# PIPduino.net
KiCad netlist of a schematic drawn in EAGLE
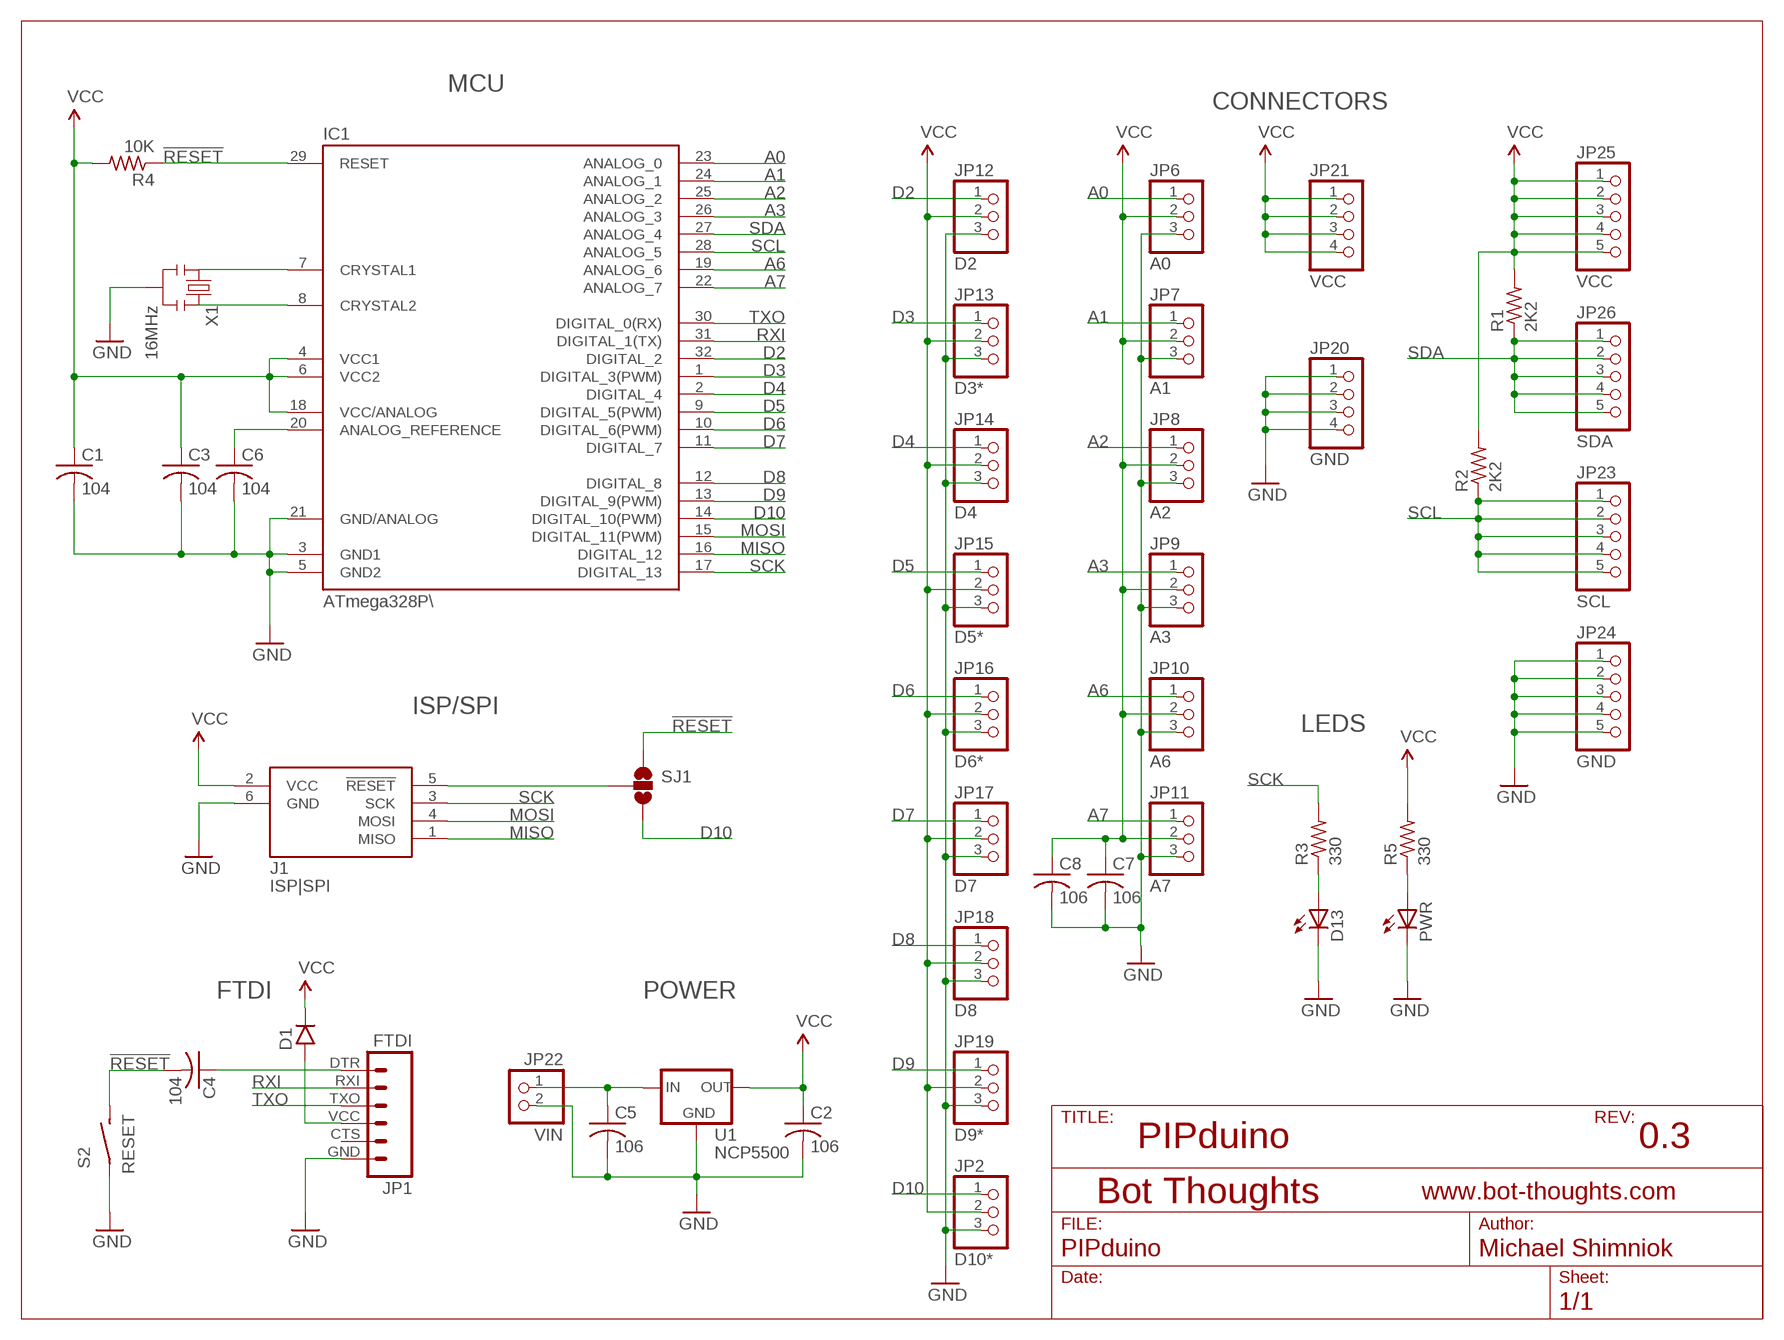
[diagram p0: schematic, sheet 1]

(export (version "E")
  (design (tool "Eeschema 10.0.6"))
  (components
    (comp (ref "C1")
      (value "104")
      (footprint "eagle-import:C0603")
      (libsource (lib "eagle-import") (part "C-USC0603"))
    )
    (comp (ref "C2")
      (value "106")
      (footprint "eagle-import:C1206")
      (libsource (lib "eagle-import") (part "C-USC1206"))
    )
    (comp (ref "C3")
      (value "104")
      (footprint "eagle-import:C0603")
      (libsource (lib "eagle-import") (part "C-USC0603"))
    )
    (comp (ref "C4")
      (value "104")
      (footprint "eagle-import:C0603")
      (libsource (lib "eagle-import") (part "C-USC0603"))
    )
    (comp (ref "C5")
      (value "106")
      (footprint "eagle-import:C1206")
      (libsource (lib "eagle-import") (part "C-USC1206"))
    )
    (comp (ref "C6")
      (value "104")
      (footprint "eagle-import:C0603")
      (libsource (lib "eagle-import") (part "C-USC0603"))
    )
    (comp (ref "C7")
      (value "106")
      (footprint "eagle-import:C1206")
      (libsource (lib "eagle-import") (part "C-USC1206"))
    )
    (comp (ref "C8")
      (value "106")
      (footprint "eagle-import:C1206")
      (libsource (lib "eagle-import") (part "C-USC1206"))
    )
    (comp (ref "D1")
      (value "DIODE_SOD123FL")
      (footprint "eagle-import:SOD123FL")
      (libsource (lib "eagle-import") (part "DIODE_SOD123FL"))
    )
    (comp (ref "D13")
      (value "LED3MM")
      (footprint "eagle-import:LED3MM")
      (libsource (lib "eagle-import") (part "LED3MM"))
    )
    (comp (ref "IC1")
      (value "ATmega328P\\")
      (footprint "eagle-import:TQFP32-08")
      (libsource (lib "eagle-import") (part "ATMEGA168-AU"))
    )
    (comp (ref "J1")
      (value "ISP|SPI")
      (footprint "eagle-import:CON6P2R")
      (libsource (lib "eagle-import") (part "AVRISP6_COMPACT"))
    )
    (comp (ref "JP1")
      (value "FTDI")
      (footprint "eagle-import:FTDI_BASIC")
      (libsource (lib "eagle-import") (part "FTDI_BASICPTH"))
    )
    (comp (ref "JP2")
      (value "D10*")
      (footprint "eagle-import:1X03-S")
      (libsource (lib "eagle-import") (part "PINHD-1X03_2.54-S"))
    )
    (comp (ref "JP6")
      (value "A0")
      (footprint "eagle-import:1X03-S")
      (libsource (lib "eagle-import") (part "PINHD-1X03_2.54-S"))
    )
    (comp (ref "JP7")
      (value "A1")
      (footprint "eagle-import:1X03-S")
      (libsource (lib "eagle-import") (part "PINHD-1X03_2.54-S"))
    )
    (comp (ref "JP8")
      (value "A2")
      (footprint "eagle-import:1X03-S")
      (libsource (lib "eagle-import") (part "PINHD-1X03_2.54-S"))
    )
    (comp (ref "JP9")
      (value "A3")
      (footprint "eagle-import:1X03-S")
      (libsource (lib "eagle-import") (part "PINHD-1X03_2.54-S"))
    )
    (comp (ref "JP10")
      (value "A6")
      (footprint "eagle-import:1X03-S")
      (libsource (lib "eagle-import") (part "PINHD-1X03_2.54-S"))
    )
    (comp (ref "JP11")
      (value "A7")
      (footprint "eagle-import:1X03-S")
      (libsource (lib "eagle-import") (part "PINHD-1X03_2.54-S"))
    )
    (comp (ref "JP12")
      (value "D2")
      (footprint "eagle-import:1X03-S")
      (libsource (lib "eagle-import") (part "PINHD-1X03_2.54-S"))
    )
    (comp (ref "JP13")
      (value "D3*")
      (footprint "eagle-import:1X03-S")
      (libsource (lib "eagle-import") (part "PINHD-1X03_2.54-S"))
    )
    (comp (ref "JP14")
      (value "D4")
      (footprint "eagle-import:1X03-S")
      (libsource (lib "eagle-import") (part "PINHD-1X03_2.54-S"))
    )
    (comp (ref "JP15")
      (value "D5*")
      (footprint "eagle-import:1X03-S")
      (libsource (lib "eagle-import") (part "PINHD-1X03_2.54-S"))
    )
    (comp (ref "JP16")
      (value "D6*")
      (footprint "eagle-import:1X03-S")
      (libsource (lib "eagle-import") (part "PINHD-1X03_2.54-S"))
    )
    (comp (ref "JP17")
      (value "D7")
      (footprint "eagle-import:1X03-S")
      (libsource (lib "eagle-import") (part "PINHD-1X03_2.54-S"))
    )
    (comp (ref "JP18")
      (value "D8")
      (footprint "eagle-import:1X03-S")
      (libsource (lib "eagle-import") (part "PINHD-1X03_2.54-S"))
    )
    (comp (ref "JP19")
      (value "D9*")
      (footprint "eagle-import:1X03-S")
      (libsource (lib "eagle-import") (part "PINHD-1X03_2.54-S"))
    )
    (comp (ref "JP20")
      (value "GND")
      (footprint "eagle-import:1X04-S")
      (libsource (lib "eagle-import") (part "PINHD-1X04_2.54-S"))
    )
    (comp (ref "JP21")
      (value "VCC")
      (footprint "eagle-import:1X04-S")
      (libsource (lib "eagle-import") (part "PINHD-1X04_2.54-S"))
    )
    (comp (ref "JP22")
      (value "VIN")
      (footprint "eagle-import:1X02-S")
      (libsource (lib "eagle-import") (part "PINHD-1X02_2.54-S"))
    )
    (comp (ref "JP23")
      (value "SCL")
      (footprint "eagle-import:1X05-S")
      (libsource (lib "eagle-import") (part "PINHD-1X05_2.54-S"))
    )
    (comp (ref "JP24")
      (value "GND")
      (footprint "eagle-import:1X05-S")
      (libsource (lib "eagle-import") (part "PINHD-1X05_2.54-S"))
    )
    (comp (ref "JP25")
      (value "VCC")
      (footprint "eagle-import:1X05-S")
      (libsource (lib "eagle-import") (part "PINHD-1X05_2.54-S"))
    )
    (comp (ref "JP26")
      (value "SDA")
      (footprint "eagle-import:1X05-S")
      (libsource (lib "eagle-import") (part "PINHD-1X05_2.54-S"))
    )
    (comp (ref "PWR")
      (value "LED3MM")
      (footprint "eagle-import:LED3MM")
      (libsource (lib "eagle-import") (part "LED3MM"))
    )
    (comp (ref "R1")
      (value "2K2")
      (footprint "eagle-import:R0603")
      (libsource (lib "eagle-import") (part "R-US_R0603"))
    )
    (comp (ref "R2")
      (value "2K2")
      (footprint "eagle-import:R0603")
      (libsource (lib "eagle-import") (part "R-US_R0603"))
    )
    (comp (ref "R3")
      (value "330")
      (footprint "eagle-import:R0603")
      (libsource (lib "eagle-import") (part "R-US_R0603"))
    )
    (comp (ref "R4")
      (value "10K")
      (footprint "eagle-import:R0603")
      (libsource (lib "eagle-import") (part "R-US_R0603"))
    )
    (comp (ref "R5")
      (value "330")
      (footprint "eagle-import:R0603")
      (libsource (lib "eagle-import") (part "R-US_R0603"))
    )
    (comp (ref "S2")
      (value "RESET")
      (footprint "eagle-import:3X4X2TACT")
      (libsource (lib "eagle-import") (part "SPST_3X4X2"))
    )
    (comp (ref "SJ1")
      (value "SOLDERJUMPER_2WAYS")
      (footprint "eagle-import:SJ_3")
      (libsource (lib "eagle-import") (part "SOLDERJUMPER_2WAYS"))
    )
    (comp (ref "U1")
      (value "NCP5500")
      (footprint "eagle-import:DPAK")
      (libsource (lib "eagle-import") (part "NCP5500"))
    )
    (comp (ref "X1")
      (value "16MHz")
      (footprint "eagle-import:CSTCE_V_C")
      (libsource (lib "eagle-import") (part "RESONATOR_CSTCE_V_C"))
    )
  )
  (nets
    (net (code "1") (name "/A0") (class "Default")
      (node (ref "IC1") (pin "23") (pinfunction "ANALOG_0_23") (pintype "bidirectional"))
      (node (ref "JP6") (pin "1") (pinfunction "1_1") (pintype "passive"))
    )
    (net (code "2") (name "/A1") (class "Default")
      (node (ref "IC1") (pin "24") (pinfunction "ANALOG_1_24") (pintype "bidirectional"))
      (node (ref "JP7") (pin "1") (pinfunction "1_1") (pintype "passive"))
    )
    (net (code "3") (name "/A2") (class "Default")
      (node (ref "IC1") (pin "25") (pinfunction "ANALOG_2_25") (pintype "bidirectional"))
      (node (ref "JP8") (pin "1") (pinfunction "1_1") (pintype "passive"))
    )
    (net (code "4") (name "/A3") (class "Default")
      (node (ref "IC1") (pin "26") (pinfunction "ANALOG_3_26") (pintype "bidirectional"))
      (node (ref "JP9") (pin "1") (pinfunction "1_1") (pintype "passive"))
    )
    (net (code "5") (name "/A6") (class "Default")
      (node (ref "IC1") (pin "19") (pinfunction "ANALOG_6_19") (pintype "passive"))
      (node (ref "JP10") (pin "1") (pinfunction "1_1") (pintype "passive"))
    )
    (net (code "6") (name "/A7") (class "Default")
      (node (ref "IC1") (pin "22") (pinfunction "ANALOG_7_22") (pintype "passive"))
      (node (ref "JP11") (pin "1") (pinfunction "1_1") (pintype "passive"))
    )
    (net (code "7") (name "/D2") (class "Default")
      (node (ref "IC1") (pin "32") (pinfunction "DIGITAL_2_32") (pintype "bidirectional"))
      (node (ref "JP12") (pin "1") (pinfunction "1_1") (pintype "passive"))
    )
    (net (code "8") (name "/D3") (class "Default")
      (node (ref "IC1") (pin "1") (pinfunction "DIGITAL_3(PWM)_1") (pintype "bidirectional"))
      (node (ref "JP13") (pin "1") (pinfunction "1_1") (pintype "passive"))
    )
    (net (code "9") (name "/D4") (class "Default")
      (node (ref "IC1") (pin "2") (pinfunction "DIGITAL_4_2") (pintype "bidirectional"))
      (node (ref "JP14") (pin "1") (pinfunction "1_1") (pintype "passive"))
    )
    (net (code "10") (name "/D5") (class "Default")
      (node (ref "IC1") (pin "9") (pinfunction "DIGITAL_5(PWM)_9") (pintype "bidirectional"))
      (node (ref "JP15") (pin "1") (pinfunction "1_1") (pintype "passive"))
    )
    (net (code "11") (name "/D6") (class "Default")
      (node (ref "IC1") (pin "10") (pinfunction "DIGITAL_6(PWM)_10") (pintype "bidirectional"))
      (node (ref "JP16") (pin "1") (pinfunction "1_1") (pintype "passive"))
    )
    (net (code "12") (name "/D7") (class "Default")
      (node (ref "IC1") (pin "11") (pinfunction "DIGITAL_7_11") (pintype "bidirectional"))
      (node (ref "JP17") (pin "1") (pinfunction "1_1") (pintype "passive"))
    )
    (net (code "13") (name "/D8") (class "Default")
      (node (ref "IC1") (pin "12") (pinfunction "DIGITAL_8_12") (pintype "bidirectional"))
      (node (ref "JP18") (pin "1") (pinfunction "1_1") (pintype "passive"))
    )
    (net (code "14") (name "/D9") (class "Default")
      (node (ref "IC1") (pin "13") (pinfunction "DIGITAL_9(PWM)_13") (pintype "bidirectional"))
      (node (ref "JP19") (pin "1") (pinfunction "1_1") (pintype "passive"))
    )
    (net (code "15") (name "/D10") (class "Default")
      (node (ref "IC1") (pin "14") (pinfunction "DIGITAL_10(PWM)_14") (pintype "bidirectional"))
      (node (ref "JP2") (pin "1") (pinfunction "1_1") (pintype "passive"))
      (node (ref "SJ1") (pin "3") (pinfunction "3_3") (pintype "passive"))
    )
    (net (code "16") (name "/MISO") (class "Default")
      (node (ref "IC1") (pin "16") (pinfunction "DIGITAL_12_16") (pintype "bidirectional"))
      (node (ref "J1") (pin "1") (pinfunction "MISO_1") (pintype "input"))
    )
    (net (code "17") (name "/MOSI") (class "Default")
      (node (ref "IC1") (pin "15") (pinfunction "DIGITAL_11(PWM)_15") (pintype "bidirectional"))
      (node (ref "J1") (pin "4") (pinfunction "MOSI_4") (pintype "output"))
    )
    (net (code "18") (name "/RXI") (class "Default")
      (node (ref "IC1") (pin "31") (pinfunction "DIGITAL_1(TX)_31") (pintype "bidirectional"))
      (node (ref "JP1") (pin "RXI") (pinfunction "2_RXI") (pintype "passive"))
    )
    (net (code "19") (name "/SCK") (class "Default")
      (node (ref "IC1") (pin "17") (pinfunction "DIGITAL_13_17") (pintype "bidirectional"))
      (node (ref "J1") (pin "3") (pinfunction "SCK_3") (pintype "output"))
      (node (ref "R3") (pin "2") (pinfunction "2_2") (pintype "passive"))
    )
    (net (code "20") (name "/SCL") (class "Default")
      (node (ref "IC1") (pin "28") (pinfunction "ANALOG_5_28") (pintype "bidirectional"))
      (node (ref "JP23") (pin "1") (pinfunction "1_1") (pintype "passive"))
      (node (ref "JP23") (pin "2") (pinfunction "2_2") (pintype "passive"))
      (node (ref "JP23") (pin "3") (pinfunction "3_3") (pintype "passive"))
      (node (ref "JP23") (pin "4") (pinfunction "4_4") (pintype "passive"))
      (node (ref "JP23") (pin "5") (pinfunction "5_5") (pintype "passive"))
      (node (ref "R2") (pin "1") (pinfunction "1_1") (pintype "passive"))
    )
    (net (code "21") (name "/SDA") (class "Default")
      (node (ref "IC1") (pin "27") (pinfunction "ANALOG_4_27") (pintype "bidirectional"))
      (node (ref "JP26") (pin "1") (pinfunction "1_1") (pintype "passive"))
      (node (ref "JP26") (pin "2") (pinfunction "2_2") (pintype "passive"))
      (node (ref "JP26") (pin "3") (pinfunction "3_3") (pintype "passive"))
      (node (ref "JP26") (pin "4") (pinfunction "4_4") (pintype "passive"))
      (node (ref "JP26") (pin "5") (pinfunction "5_5") (pintype "passive"))
      (node (ref "R1") (pin "1") (pinfunction "1_1") (pintype "passive"))
    )
    (net (code "22") (name "/TXO") (class "Default")
      (node (ref "IC1") (pin "30") (pinfunction "DIGITAL_0(RX)_30") (pintype "bidirectional"))
      (node (ref "JP1") (pin "TXO") (pinfunction "3_TXO") (pintype "passive"))
    )
    (net (code "23") (name "/~{RESET}") (class "Default")
      (node (ref "C4") (pin "2") (pinfunction "2_2") (pintype "passive"))
      (node (ref "IC1") (pin "29") (pinfunction "RESET_29") (pintype "bidirectional"))
      (node (ref "R4") (pin "1") (pinfunction "1_1") (pintype "passive"))
      (node (ref "S2") (pin "P$2") (pinfunction "S_P$2") (pintype "passive"))
      (node (ref "SJ1") (pin "1") (pinfunction "1_1") (pintype "passive"))
    )
    (net (code "24") (name "GND") (class "Default")
      (node (ref "C1") (pin "2") (pinfunction "2_2") (pintype "passive"))
      (node (ref "C2") (pin "2") (pinfunction "2_2") (pintype "passive"))
      (node (ref "C3") (pin "2") (pinfunction "2_2") (pintype "passive"))
      (node (ref "C5") (pin "2") (pinfunction "2_2") (pintype "passive"))
      (node (ref "C6") (pin "2") (pinfunction "2_2") (pintype "passive"))
      (node (ref "C7") (pin "2") (pinfunction "2_2") (pintype "passive"))
      (node (ref "C8") (pin "2") (pinfunction "2_2") (pintype "passive"))
      (node (ref "D13") (pin "K") (pinfunction "C_K") (pintype "passive"))
      (node (ref "IC1") (pin "21") (pinfunction "GND/ANALOG_21") (pintype "power_in"))
      (node (ref "IC1") (pin "3") (pinfunction "GND1_3") (pintype "power_in"))
      (node (ref "IC1") (pin "5") (pinfunction "GND2_5") (pintype "power_in"))
      (node (ref "J1") (pin "6") (pinfunction "GND_6") (pintype "power_in"))
      (node (ref "JP1") (pin "GND") (pinfunction "6_GND") (pintype "passive"))
      (node (ref "JP10") (pin "3") (pinfunction "3_3") (pintype "passive"))
      (node (ref "JP11") (pin "3") (pinfunction "3_3") (pintype "passive"))
      (node (ref "JP12") (pin "3") (pinfunction "3_3") (pintype "passive"))
      (node (ref "JP13") (pin "3") (pinfunction "3_3") (pintype "passive"))
      (node (ref "JP14") (pin "3") (pinfunction "3_3") (pintype "passive"))
      (node (ref "JP15") (pin "3") (pinfunction "3_3") (pintype "passive"))
      (node (ref "JP16") (pin "3") (pinfunction "3_3") (pintype "passive"))
      (node (ref "JP17") (pin "3") (pinfunction "3_3") (pintype "passive"))
      (node (ref "JP18") (pin "3") (pinfunction "3_3") (pintype "passive"))
      (node (ref "JP19") (pin "3") (pinfunction "3_3") (pintype "passive"))
      (node (ref "JP2") (pin "3") (pinfunction "3_3") (pintype "passive"))
      (node (ref "JP20") (pin "1") (pinfunction "1_1") (pintype "passive"))
      (node (ref "JP20") (pin "2") (pinfunction "2_2") (pintype "passive"))
      (node (ref "JP20") (pin "3") (pinfunction "3_3") (pintype "passive"))
      (node (ref "JP20") (pin "4") (pinfunction "4_4") (pintype "passive"))
      (node (ref "JP22") (pin "2") (pinfunction "2_2") (pintype "passive"))
      (node (ref "JP24") (pin "1") (pinfunction "1_1") (pintype "passive"))
      (node (ref "JP24") (pin "2") (pinfunction "2_2") (pintype "passive"))
      (node (ref "JP24") (pin "3") (pinfunction "3_3") (pintype "passive"))
      (node (ref "JP24") (pin "4") (pinfunction "4_4") (pintype "passive"))
      (node (ref "JP24") (pin "5") (pinfunction "5_5") (pintype "passive"))
      (node (ref "JP6") (pin "3") (pinfunction "3_3") (pintype "passive"))
      (node (ref "JP7") (pin "3") (pinfunction "3_3") (pintype "passive"))
      (node (ref "JP8") (pin "3") (pinfunction "3_3") (pintype "passive"))
      (node (ref "JP9") (pin "3") (pinfunction "3_3") (pintype "passive"))
      (node (ref "PWR") (pin "K") (pinfunction "C_K") (pintype "passive"))
      (node (ref "S2") (pin "P$1") (pinfunction "P_P$1") (pintype "passive"))
      (node (ref "U1") (pin "4") (pinfunction "GND_4") (pintype "bidirectional"))
      (node (ref "X1") (pin "GND") (pinfunction "GND_GND") (pintype "passive"))
    )
    (net (code "25") (name "Net-(D13-PadA)") (class "Default")
      (node (ref "D13") (pin "A") (pinfunction "A_A") (pintype "passive"))
      (node (ref "R3") (pin "1") (pinfunction "1_1") (pintype "passive"))
    )
    (net (code "26") (name "Net-(IC1-ANALOG_REFERENCE)") (class "Default")
      (node (ref "C6") (pin "1") (pinfunction "1_1") (pintype "passive"))
      (node (ref "IC1") (pin "20") (pinfunction "ANALOG_REFERENCE_20") (pintype "passive"))
    )
    (net (code "27") (name "Net-(IC1-CRYSTAL1)") (class "Default")
      (node (ref "IC1") (pin "7") (pinfunction "CRYSTAL1_7") (pintype "bidirectional"))
      (node (ref "X1") (pin "X1") (pinfunction "X1_X1") (pintype "passive"))
    )
    (net (code "28") (name "Net-(IC1-CRYSTAL2)") (class "Default")
      (node (ref "IC1") (pin "8") (pinfunction "CRYSTAL2_8") (pintype "bidirectional"))
      (node (ref "X1") (pin "X2") (pinfunction "X2_X2") (pintype "passive"))
    )
    (net (code "29") (name "Net-(J1-~{RESET})") (class "Default")
      (node (ref "J1") (pin "5") (pinfunction "~{RESET}_5") (pintype "output"))
      (node (ref "SJ1") (pin "2") (pinfunction "2_2") (pintype "passive"))
    )
    (net (code "30") (name "Net-(JP1-1)") (class "Default")
      (node (ref "C4") (pin "1") (pinfunction "1_1") (pintype "passive"))
      (node (ref "JP1") (pin "DTR") (pinfunction "1_DTR") (pintype "passive"))
    )
    (net (code "31") (name "Net-(JP1-4)") (class "Default")
      (node (ref "D1") (pin "A") (pinfunction "A_A") (pintype "passive"))
      (node (ref "JP1") (pin "VCC") (pinfunction "4_VCC") (pintype "passive"))
    )
    (net (code "32") (name "Net-(PWR-PadA)") (class "Default")
      (node (ref "PWR") (pin "A") (pinfunction "A_A") (pintype "passive"))
      (node (ref "R5") (pin "1") (pinfunction "1_1") (pintype "passive"))
    )
    (net (code "33") (name "Net-(U1-VIN)") (class "Default")
      (node (ref "C5") (pin "1") (pinfunction "1_1") (pintype "passive"))
      (node (ref "JP22") (pin "1") (pinfunction "1_1") (pintype "passive"))
      (node (ref "U1") (pin "1") (pinfunction "VIN_1") (pintype "bidirectional"))
    )
    (net (code "34") (name "VCC") (class "Default")
      (node (ref "C1") (pin "1") (pinfunction "1_1") (pintype "passive"))
      (node (ref "C2") (pin "1") (pinfunction "1_1") (pintype "passive"))
      (node (ref "C3") (pin "1") (pinfunction "1_1") (pintype "passive"))
      (node (ref "C7") (pin "1") (pinfunction "1_1") (pintype "passive"))
      (node (ref "C8") (pin "1") (pinfunction "1_1") (pintype "passive"))
      (node (ref "D1") (pin "C") (pinfunction "C_C") (pintype "passive"))
      (node (ref "IC1") (pin "18") (pinfunction "VCC/ANALOG_18") (pintype "passive"))
      (node (ref "IC1") (pin "4") (pinfunction "VCC1_4") (pintype "power_in"))
      (node (ref "IC1") (pin "6") (pinfunction "VCC2_6") (pintype "power_in"))
      (node (ref "J1") (pin "2") (pinfunction "VCC_2") (pintype "power_in"))
      (node (ref "JP10") (pin "2") (pinfunction "2_2") (pintype "passive"))
      (node (ref "JP11") (pin "2") (pinfunction "2_2") (pintype "passive"))
      (node (ref "JP12") (pin "2") (pinfunction "2_2") (pintype "passive"))
      (node (ref "JP13") (pin "2") (pinfunction "2_2") (pintype "passive"))
      (node (ref "JP14") (pin "2") (pinfunction "2_2") (pintype "passive"))
      (node (ref "JP15") (pin "2") (pinfunction "2_2") (pintype "passive"))
      (node (ref "JP16") (pin "2") (pinfunction "2_2") (pintype "passive"))
      (node (ref "JP17") (pin "2") (pinfunction "2_2") (pintype "passive"))
      (node (ref "JP18") (pin "2") (pinfunction "2_2") (pintype "passive"))
      (node (ref "JP19") (pin "2") (pinfunction "2_2") (pintype "passive"))
      (node (ref "JP2") (pin "2") (pinfunction "2_2") (pintype "passive"))
      (node (ref "JP21") (pin "1") (pinfunction "1_1") (pintype "passive"))
      (node (ref "JP21") (pin "2") (pinfunction "2_2") (pintype "passive"))
      (node (ref "JP21") (pin "3") (pinfunction "3_3") (pintype "passive"))
      (node (ref "JP21") (pin "4") (pinfunction "4_4") (pintype "passive"))
      (node (ref "JP25") (pin "1") (pinfunction "1_1") (pintype "passive"))
      (node (ref "JP25") (pin "2") (pinfunction "2_2") (pintype "passive"))
      (node (ref "JP25") (pin "3") (pinfunction "3_3") (pintype "passive"))
      (node (ref "JP25") (pin "4") (pinfunction "4_4") (pintype "passive"))
      (node (ref "JP25") (pin "5") (pinfunction "5_5") (pintype "passive"))
      (node (ref "JP6") (pin "2") (pinfunction "2_2") (pintype "passive"))
      (node (ref "JP7") (pin "2") (pinfunction "2_2") (pintype "passive"))
      (node (ref "JP8") (pin "2") (pinfunction "2_2") (pintype "passive"))
      (node (ref "JP9") (pin "2") (pinfunction "2_2") (pintype "passive"))
      (node (ref "R1") (pin "2") (pinfunction "2_2") (pintype "passive"))
      (node (ref "R2") (pin "2") (pinfunction "2_2") (pintype "passive"))
      (node (ref "R4") (pin "2") (pinfunction "2_2") (pintype "passive"))
      (node (ref "R5") (pin "2") (pinfunction "2_2") (pintype "passive"))
      (node (ref "U1") (pin "3") (pinfunction "VOUT_3") (pintype "bidirectional"))
    )
    (net (code "35") (name "unconnected-(JP1-5-PadCTS)") (class "Default")
      (node (ref "JP1") (pin "CTS") (pinfunction "5_CTS") (pintype "passive"))
    )
  )
)
